# week5.net
KiCad netlist of a schematic drawn in EAGLE
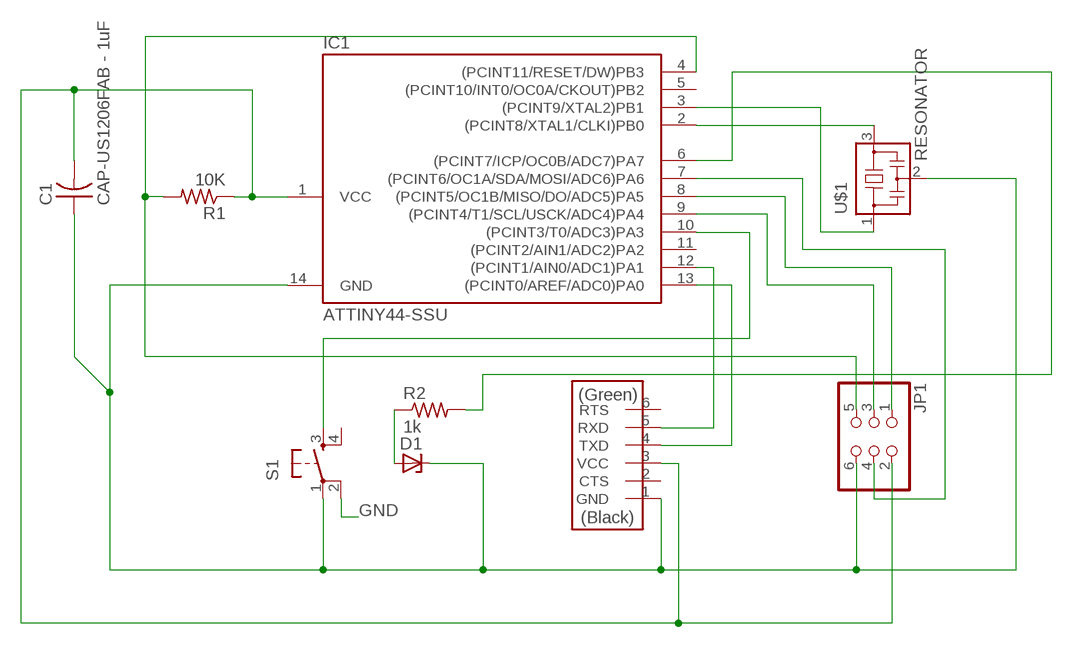
[diagram p0: schematic, sheet 1]

(export (version "E")
  (design (tool "Eeschema 10.0.6"))
  (components
    (comp (ref "C1")
      (value "CAP-US1206FAB - 1uF")
      (footprint "eagle-import:C1206FAB")
      (libsource (lib "eagle-import") (part "CAP-US1206FAB"))
    )
    (comp (ref "D1")
      (value "ZENER_DIODESOD123")
      (footprint "eagle-import:SOD123")
      (libsource (lib "eagle-import") (part "ZENER_DIODESOD123"))
    )
    (comp (ref "IC1")
      (value "ATTINY44-SSU")
      (footprint "eagle-import:SOIC14")
      (libsource (lib "eagle-import") (part "ATTINY44-SSU"))
    )
    (comp (ref "JP1")
      (value "PINHD-2X3-SMD")
      (footprint "eagle-import:2X03SMD")
      (libsource (lib "eagle-import") (part "PINHD-2X3-SMD"))
    )
    (comp (ref "R1")
      (value "10K")
      (footprint "eagle-import:R1206")
      (libsource (lib "eagle-import") (part "RES-US1206"))
    )
    (comp (ref "R2")
      (value "1k")
      (footprint "eagle-import:R1206FAB")
      (libsource (lib "eagle-import") (part "RES-US1206FAB"))
    )
    (comp (ref "S1")
      (value "6MM_SWITCH6MM_SWITCH")
      (footprint "eagle-import:6MM_SWITCH")
      (libsource (lib "eagle-import") (part "6MM_SWITCH6MM_SWITCH"))
    )
    (comp (ref "U$1")
      (value "RESONATOR")
      (footprint "eagle-import:EFOBM")
      (libsource (lib "eagle-import") (part "RESONATOR"))
    )
    (comp (ref "U$2")
      (value "FTDI-SMD-HEADER")
      (footprint "eagle-import:1X06SMD")
      (libsource (lib "eagle-import") (part "FTDI-SMD-HEADER"))
    )
  )
  (nets
    (net (code "1") (name "/GND") (class "Default")
      (node (ref "C1") (pin "1") (pinfunction "1_1") (pintype "passive"))
      (node (ref "D1") (pin "CATHODE") (pinfunction "CATHODE_CATHODE") (pintype "passive"))
      (node (ref "IC1") (pin "14") (pinfunction "GND_14") (pintype "power_in"))
      (node (ref "JP1") (pin "6") (pinfunction "6_6") (pintype "passive"))
      (node (ref "S1") (pin "1") (pinfunction "P_1") (pintype "passive"))
      (node (ref "S1") (pin "2") (pinfunction "P1_2") (pintype "passive"))
      (node (ref "U$1") (pin "2") (pinfunction "2_2") (pintype "passive"))
      (node (ref "U$2") (pin "1") (pinfunction "GND_1") (pintype "bidirectional"))
    )
    (net (code "2") (name "Net-(D1-PadANODE)") (class "Default")
      (node (ref "D1") (pin "ANODE") (pinfunction "ANODE_ANODE") (pintype "passive"))
      (node (ref "R2") (pin "1") (pinfunction "1_1") (pintype "passive"))
    )
    (net (code "3") (name "Net-(IC1-(PCINT0{slash}AREF{slash}ADC0)PA0)") (class "Default")
      (node (ref "IC1") (pin "13") (pinfunction "(PCINT0/AREF/ADC0)PA0_13") (pintype "bidirectional"))
      (node (ref "U$2") (pin "4") (pinfunction "TXD_4") (pintype "bidirectional"))
    )
    (net (code "4") (name "Net-(IC1-(PCINT1{slash}AIN0{slash}ADC1)PA1)") (class "Default")
      (node (ref "IC1") (pin "12") (pinfunction "(PCINT1/AIN0/ADC1)PA1_12") (pintype "bidirectional"))
      (node (ref "U$2") (pin "5") (pinfunction "RXD_5") (pintype "bidirectional"))
    )
    (net (code "5") (name "Net-(IC1-(PCINT3{slash}T0{slash}ADC3)PA3)") (class "Default")
      (node (ref "IC1") (pin "10") (pinfunction "(PCINT3/T0/ADC3)PA3_10") (pintype "bidirectional"))
      (node (ref "S1") (pin "3") (pinfunction "S_3") (pintype "passive"))
    )
    (net (code "6") (name "Net-(IC1-(PCINT4{slash}T1{slash}SCL{slash}USCK{slash}ADC4)PA4)") (class "Default")
      (node (ref "IC1") (pin "9") (pinfunction "(PCINT4/T1/SCL/USCK/ADC4)PA4_9") (pintype "bidirectional"))
      (node (ref "JP1") (pin "3") (pinfunction "3_3") (pintype "passive"))
    )
    (net (code "7") (name "Net-(IC1-(PCINT5{slash}OC1B{slash}MISO{slash}DO{slash}ADC5)PA5)") (class "Default")
      (node (ref "IC1") (pin "8") (pinfunction "(PCINT5/OC1B/MISO/DO/ADC5)PA5_8") (pintype "bidirectional"))
      (node (ref "JP1") (pin "1") (pinfunction "1_1") (pintype "passive"))
    )
    (net (code "8") (name "Net-(IC1-(PCINT6{slash}OC1A{slash}SDA{slash}MOSI{slash}ADC6)PA6)") (class "Default")
      (node (ref "IC1") (pin "7") (pinfunction "(PCINT6/OC1A/SDA/MOSI/ADC6)PA6_7") (pintype "bidirectional"))
      (node (ref "JP1") (pin "4") (pinfunction "4_4") (pintype "passive"))
    )
    (net (code "9") (name "Net-(IC1-(PCINT7{slash}ICP{slash}OC0B{slash}ADC7)PA7)") (class "Default")
      (node (ref "IC1") (pin "6") (pinfunction "(PCINT7/ICP/OC0B/ADC7)PA7_6") (pintype "bidirectional"))
      (node (ref "R2") (pin "2") (pinfunction "2_2") (pintype "passive"))
    )
    (net (code "10") (name "Net-(IC1-(PCINT8{slash}XTAL1{slash}CLKI)PB0)") (class "Default")
      (node (ref "IC1") (pin "2") (pinfunction "(PCINT8/XTAL1/CLKI)PB0_2") (pintype "bidirectional"))
      (node (ref "U$1") (pin "3") (pinfunction "3_3") (pintype "passive"))
    )
    (net (code "11") (name "Net-(IC1-(PCINT9{slash}XTAL2)PB1)") (class "Default")
      (node (ref "IC1") (pin "3") (pinfunction "(PCINT9/XTAL2)PB1_3") (pintype "bidirectional"))
      (node (ref "U$1") (pin "1") (pinfunction "1_1") (pintype "passive"))
    )
    (net (code "12") (name "Net-(IC1-(PCINT11{slash}RESET{slash}DW)PB3)") (class "Default")
      (node (ref "IC1") (pin "4") (pinfunction "(PCINT11/RESET/DW)PB3_4") (pintype "bidirectional"))
      (node (ref "JP1") (pin "5") (pinfunction "5_5") (pintype "passive"))
      (node (ref "R1") (pin "2") (pinfunction "2_2") (pintype "passive"))
    )
    (net (code "13") (name "Net-(IC1-VCC)") (class "Default")
      (node (ref "C1") (pin "2") (pinfunction "2_2") (pintype "passive"))
      (node (ref "IC1") (pin "1") (pinfunction "VCC_1") (pintype "power_in"))
      (node (ref "JP1") (pin "2") (pinfunction "2_2") (pintype "passive"))
      (node (ref "R1") (pin "1") (pinfunction "1_1") (pintype "passive"))
      (node (ref "U$2") (pin "3") (pinfunction "VCC_3") (pintype "bidirectional"))
    )
    (net (code "14") (name "unconnected-(IC1-(PCINT2{slash}AIN1{slash}ADC2)PA2-Pad11)") (class "Default")
      (node (ref "IC1") (pin "11") (pinfunction "(PCINT2/AIN1/ADC2)PA2_11") (pintype "bidirectional"))
    )
    (net (code "15") (name "unconnected-(IC1-(PCINT10{slash}INT0{slash}OC0A{slash}CKOUT)PB2-Pad5)") (class "Default")
      (node (ref "IC1") (pin "5") (pinfunction "(PCINT10/INT0/OC0A/CKOUT)PB2_5") (pintype "bidirectional"))
    )
    (net (code "16") (name "unconnected-(S1-S1-Pad4)") (class "Default")
      (node (ref "S1") (pin "4") (pinfunction "S1_4") (pintype "passive"))
    )
    (net (code "17") (name "unconnected-(U$2-CTS-Pad2)") (class "Default")
      (node (ref "U$2") (pin "2") (pinfunction "CTS_2") (pintype "bidirectional"))
    )
    (net (code "18") (name "unconnected-(U$2-RTS-Pad6)") (class "Default")
      (node (ref "U$2") (pin "6") (pinfunction "RTS_6") (pintype "bidirectional"))
    )
  )
)
